# Ethernet_Interface.net
KiCad netlist of a schematic drawn in Altium Designer
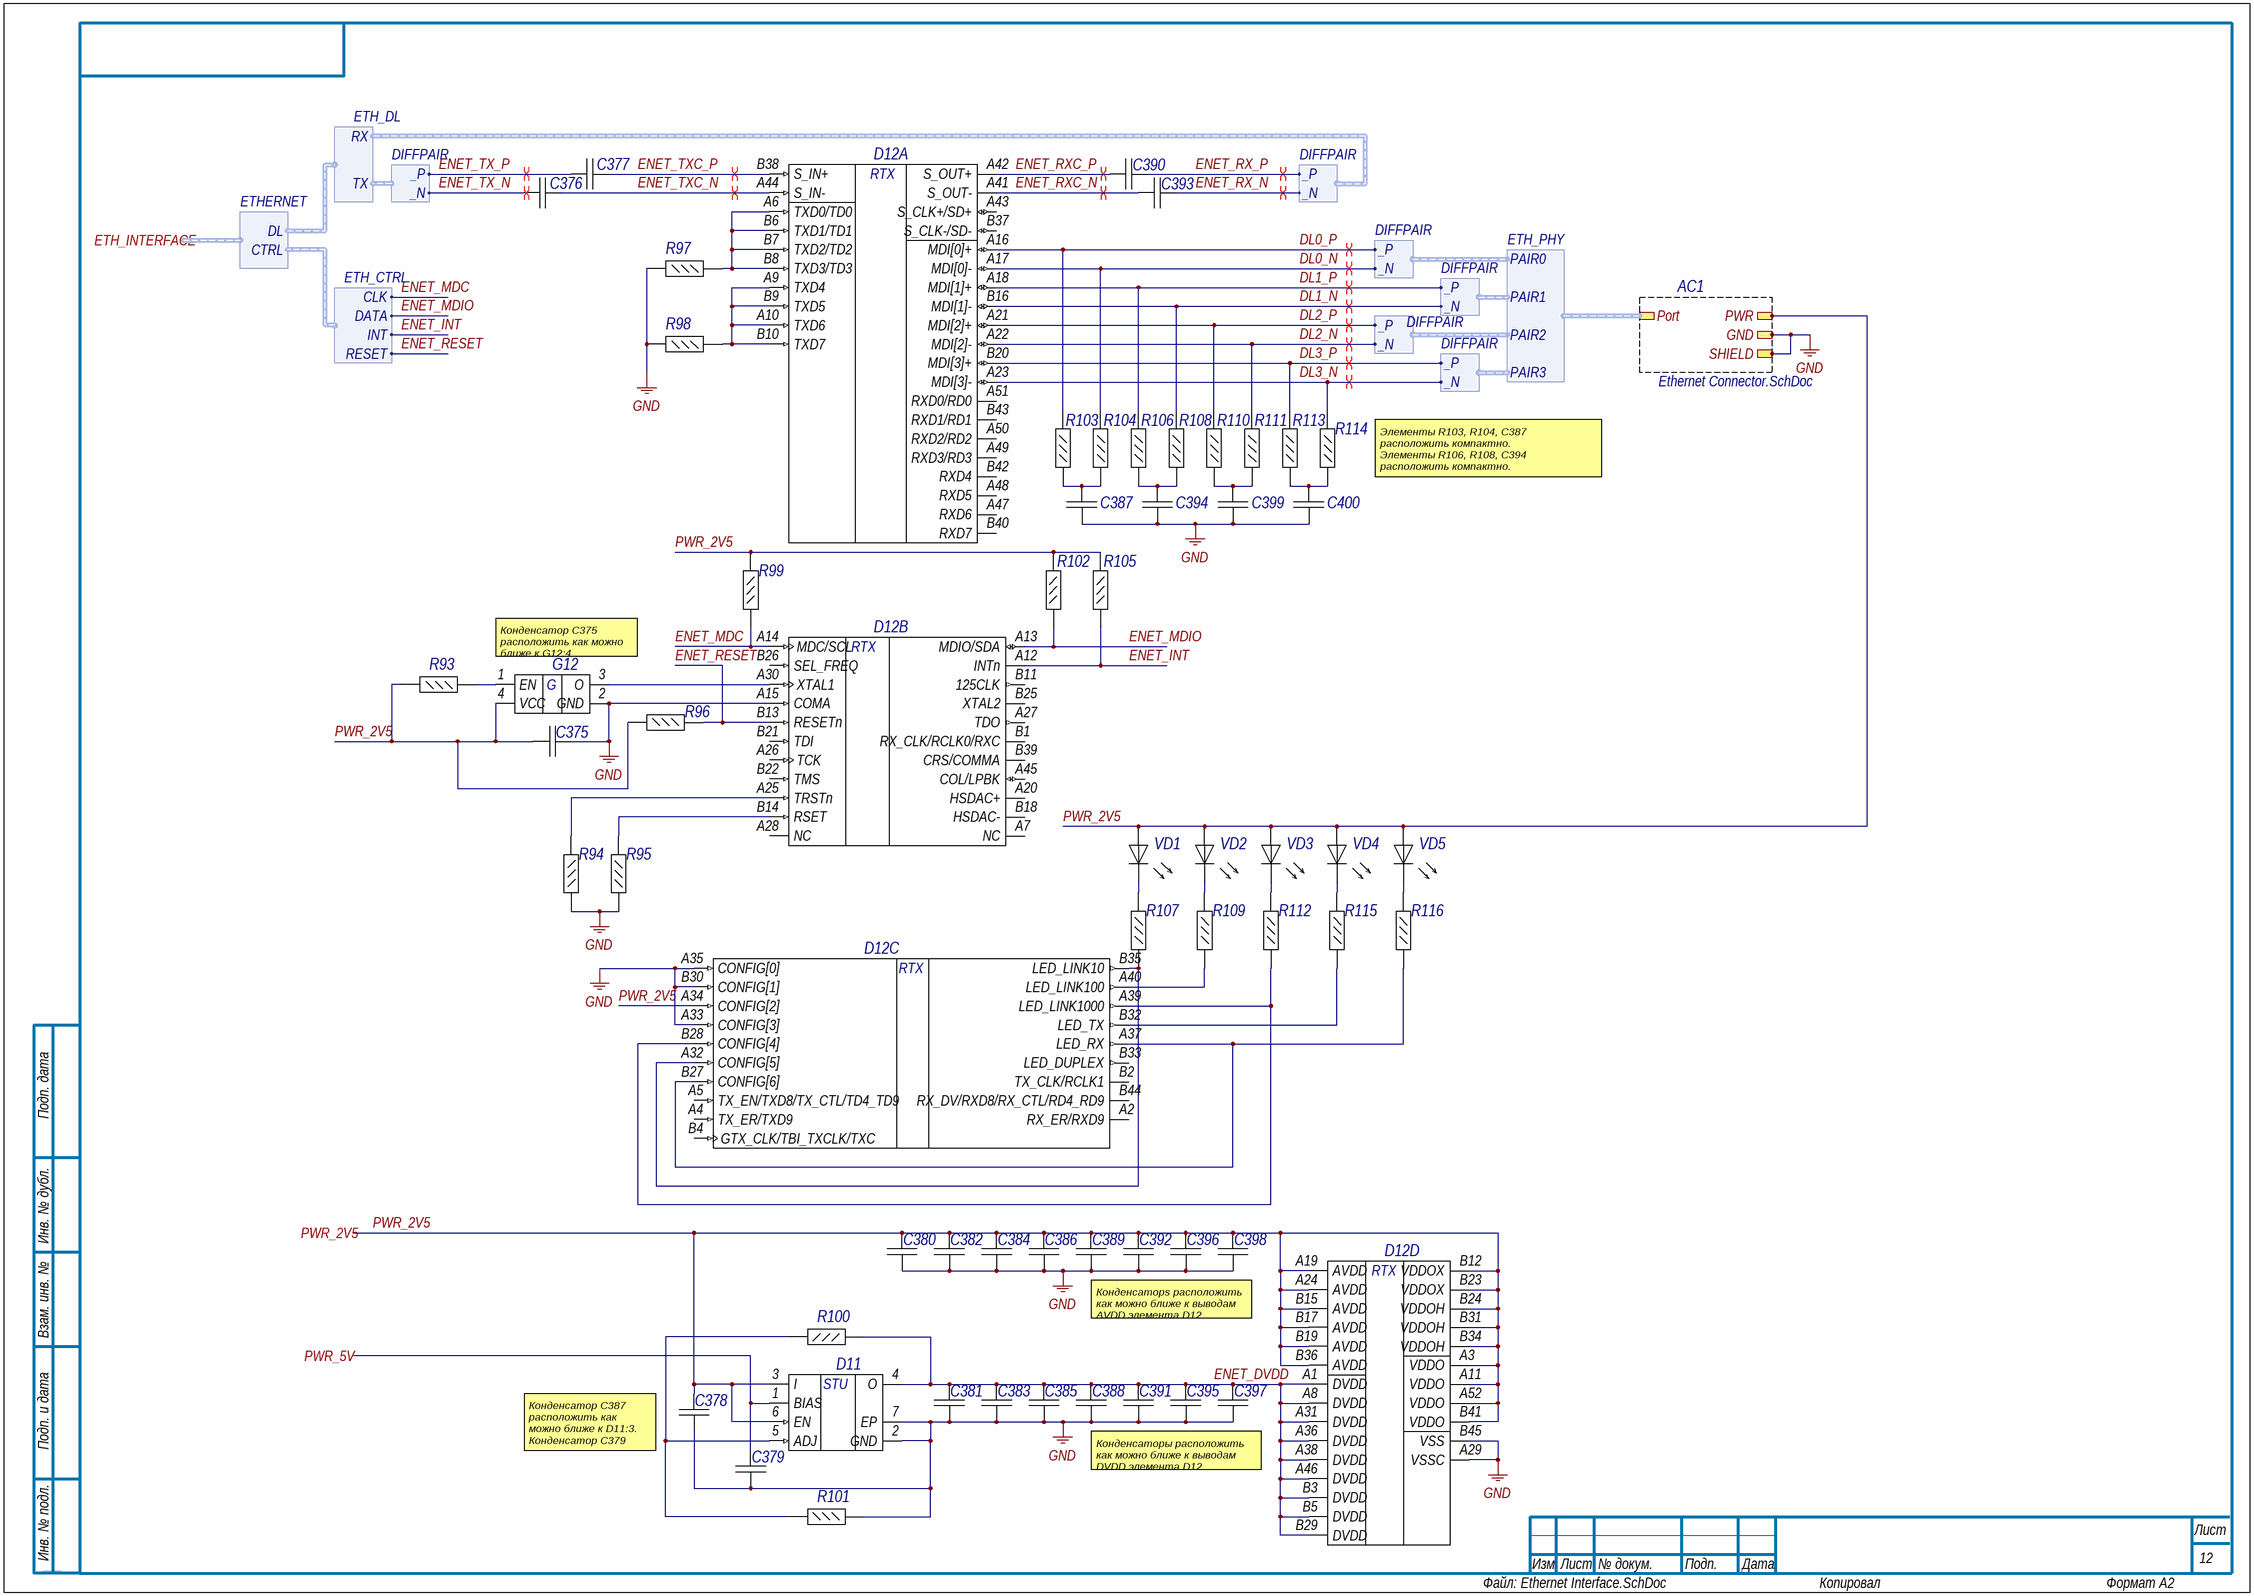
[diagram p0: Ethernet Interface.SchDoc]

(export (version "E")
  (design (tool "Eeschema 10.0.6"))
  (components
    (comp (ref "C375")
      (value "GRM155R71H103KA88D")
      (footprint "CAPC1005X55X25ML05T10")
      (description "Chip Capacitor, 10 nF, +/- 10%, 50 V, -55 to 125 degC, 0402 (1005 Metric), RoHS, Tape and Reel")
      (fields (field (name "TOLERANCE") "10%") (field (name "MANUFACTURER") "Basic Passives"))
      (libsource (lib "MiniPC DB") (part "CAP_NP"))
    )
    (comp (ref "C376")
      (value "C1005X7R1E104M")
      (footprint "CAPC1005X55X10LL05")
      (description "Chip Capacitor, 0.1 uF, +/- 20%, 25 V, -55 to 125 degC, 0402 (1005 Metric), RoHS, Tape and Reel")
      (fields (field (name "TOLERANCE") "20%"))
      (libsource (lib "MiniPC DB") (part "CAP_NP"))
    )
    (comp (ref "C377")
      (value "C1005X7R1E104M")
      (footprint "CAPC1005X55X10LL05")
      (description "Chip Capacitor, 0.1 uF, +/- 20%, 25 V, -55 to 125 degC, 0402 (1005 Metric), RoHS, Tape and Reel")
      (fields (field (name "TOLERANCE") "20%"))
      (libsource (lib "MiniPC DB") (part "CAP_NP"))
    )
    (comp (ref "C378")
      (value "C2012X5R1C106K085AC")
      (footprint "CAPC2013X100X20NL20")
      (description "Chip Capacitor, 10 uF, +/- 10%, 16 V, -55 to 85 degC, 0805 (2012 Metric), RoHS, Tape and Reel")
      (fields (field (name "TOLERANCE") "10%"))
      (libsource (lib "MiniPC DB") (part "CAP_NP"))
    )
    (comp (ref "C379")
      (value "CGB2A1X5R1E105K033BC")
      (footprint "CAPC1005X33X10LL5")
      (description "Chip Capacitor, 1 uF, +/- 10%, 25 V, -55 to 85 degC, 0402 (1005 Metric), RoHS, Tape and Reel")
      (fields (field (name "TOLERANCE") "10%"))
      (libsource (lib "MiniPC DB") (part "CAP_NP"))
    )
    (comp (ref "C380")
      (value "C1005X7R1E104M")
      (footprint "CAPC1005X55X10LL05")
      (description "Chip Capacitor, 0.1 uF, +/- 20%, 25 V, -55 to 125 degC, 0402 (1005 Metric), RoHS, Tape and Reel")
      (fields (field (name "TOLERANCE") "20%"))
      (libsource (lib "MiniPC DB") (part "CAP_NP"))
    )
    (comp (ref "C381")
      (value "GRM31CR61E226KE15L")
      (footprint "CAPC3216X180X55ML20T25")
      (description "Chip Capacitor, 22 uF, +/- 10%, 25 V, -55 to 85 degC, 1206 (3216 Metric), RoHS, Tape and Reel")
      (fields (field (name "TOLERANCE") "10%"))
      (libsource (lib "MiniPC DB") (part "CAP_NP"))
    )
    (comp (ref "C382")
      (value "C1005X7R1E104M")
      (footprint "CAPC1005X55X10LL05")
      (description "Chip Capacitor, 0.1 uF, +/- 20%, 25 V, -55 to 125 degC, 0402 (1005 Metric), RoHS, Tape and Reel")
      (fields (field (name "TOLERANCE") "20%"))
      (libsource (lib "MiniPC DB") (part "CAP_NP"))
    )
    (comp (ref "C383")
      (value "GRM188R61A225KE34x")
      (footprint "CAPC1608X90X35ML10T15")
      (description "Chip Capacitor, 2.2 uF, +/- 10%, 10 V, -55 to 85 degC, 0603 (1608 Metric), RoHS, Tape and Reel")
      (fields (field (name "TOLERANCE") "10%"))
      (libsource (lib "MiniPC DB") (part "CAP_NP"))
    )
    (comp (ref "C384")
      (value "C1005X7R1E104M")
      (footprint "CAPC1005X55X10LL05")
      (description "Chip Capacitor, 0.1 uF, +/- 20%, 25 V, -55 to 125 degC, 0402 (1005 Metric), RoHS, Tape and Reel")
      (fields (field (name "TOLERANCE") "20%"))
      (libsource (lib "MiniPC DB") (part "CAP_NP"))
    )
    (comp (ref "C385")
      (value "C1005X7R1E104M")
      (footprint "CAPC1005X55X10LL05")
      (description "Chip Capacitor, 0.1 uF, +/- 20%, 25 V, -55 to 125 degC, 0402 (1005 Metric), RoHS, Tape and Reel")
      (fields (field (name "TOLERANCE") "20%"))
      (libsource (lib "MiniPC DB") (part "CAP_NP"))
    )
    (comp (ref "C386")
      (value "C1005X7R1E104M")
      (footprint "CAPC1005X55X10LL05")
      (description "Chip Capacitor, 0.1 uF, +/- 20%, 25 V, -55 to 125 degC, 0402 (1005 Metric), RoHS, Tape and Reel")
      (fields (field (name "TOLERANCE") "20%"))
      (libsource (lib "MiniPC DB") (part "CAP_NP"))
    )
    (comp (ref "C387")
      (value "GRM155R71H103KA88D")
      (footprint "CAPC1005X55X25ML05T10")
      (description "Chip Capacitor, 10 nF, +/- 10%, 50 V, -55 to 125 degC, 0402 (1005 Metric), RoHS, Tape and Reel")
      (fields (field (name "TOLERANCE") "10%") (field (name "MANUFACTURER") "Basic Passives"))
      (libsource (lib "MiniPC DB") (part "CAP_NP"))
    )
    (comp (ref "C388")
      (value "C1005X7R1E104M")
      (footprint "CAPC1005X55X10LL05")
      (description "Chip Capacitor, 0.1 uF, +/- 20%, 25 V, -55 to 125 degC, 0402 (1005 Metric), RoHS, Tape and Reel")
      (fields (field (name "TOLERANCE") "20%"))
      (libsource (lib "MiniPC DB") (part "CAP_NP"))
    )
    (comp (ref "C389")
      (value "C1005X7R1E104M")
      (footprint "CAPC1005X55X10LL05")
      (description "Chip Capacitor, 0.1 uF, +/- 20%, 25 V, -55 to 125 degC, 0402 (1005 Metric), RoHS, Tape and Reel")
      (fields (field (name "TOLERANCE") "20%"))
      (libsource (lib "MiniPC DB") (part "CAP_NP"))
    )
    (comp (ref "C390")
      (value "C1005X7R1E104M")
      (footprint "CAPC1005X55X10LL05")
      (description "Chip Capacitor, 0.1 uF, +/- 20%, 25 V, -55 to 125 degC, 0402 (1005 Metric), RoHS, Tape and Reel")
      (fields (field (name "TOLERANCE") "20%"))
      (libsource (lib "MiniPC DB") (part "CAP_NP"))
    )
    (comp (ref "C391")
      (value "C1005X7R1E104M")
      (footprint "CAPC1005X55X10LL05")
      (description "Chip Capacitor, 0.1 uF, +/- 20%, 25 V, -55 to 125 degC, 0402 (1005 Metric), RoHS, Tape and Reel")
      (fields (field (name "TOLERANCE") "20%"))
      (libsource (lib "MiniPC DB") (part "CAP_NP"))
    )
    (comp (ref "C392")
      (value "C1005X7R1E104M")
      (footprint "CAPC1005X55X10LL05")
      (description "Chip Capacitor, 0.1 uF, +/- 20%, 25 V, -55 to 125 degC, 0402 (1005 Metric), RoHS, Tape and Reel")
      (fields (field (name "TOLERANCE") "20%"))
      (libsource (lib "MiniPC DB") (part "CAP_NP"))
    )
    (comp (ref "C393")
      (value "C1005X7R1E104M")
      (footprint "CAPC1005X55X10LL05")
      (description "Chip Capacitor, 0.1 uF, +/- 20%, 25 V, -55 to 125 degC, 0402 (1005 Metric), RoHS, Tape and Reel")
      (fields (field (name "TOLERANCE") "20%"))
      (libsource (lib "MiniPC DB") (part "CAP_NP"))
    )
    (comp (ref "C394")
      (value "GRM155R71H103KA88D")
      (footprint "CAPC1005X55X25ML05T10")
      (description "Chip Capacitor, 10 nF, +/- 10%, 50 V, -55 to 125 degC, 0402 (1005 Metric), RoHS, Tape and Reel")
      (fields (field (name "TOLERANCE") "10%") (field (name "MANUFACTURER") "Basic Passives"))
      (libsource (lib "MiniPC DB") (part "CAP_NP"))
    )
    (comp (ref "C395")
      (value "C1005X7R1E104M")
      (footprint "CAPC1005X55X10LL05")
      (description "Chip Capacitor, 0.1 uF, +/- 20%, 25 V, -55 to 125 degC, 0402 (1005 Metric), RoHS, Tape and Reel")
      (fields (field (name "TOLERANCE") "20%"))
      (libsource (lib "MiniPC DB") (part "CAP_NP"))
    )
    (comp (ref "C396")
      (value "C1005X7R1E104M")
      (footprint "CAPC1005X55X10LL05")
      (description "Chip Capacitor, 0.1 uF, +/- 20%, 25 V, -55 to 125 degC, 0402 (1005 Metric), RoHS, Tape and Reel")
      (fields (field (name "TOLERANCE") "20%"))
      (libsource (lib "MiniPC DB") (part "CAP_NP"))
    )
    (comp (ref "C397")
      (value "C1005X7R1E104M")
      (footprint "CAPC1005X55X10LL05")
      (description "Chip Capacitor, 0.1 uF, +/- 20%, 25 V, -55 to 125 degC, 0402 (1005 Metric), RoHS, Tape and Reel")
      (fields (field (name "TOLERANCE") "20%"))
      (libsource (lib "MiniPC DB") (part "CAP_NP"))
    )
    (comp (ref "C398")
      (value "C1005X7R1E104M")
      (footprint "CAPC1005X55X10LL05")
      (description "Chip Capacitor, 0.1 uF, +/- 20%, 25 V, -55 to 125 degC, 0402 (1005 Metric), RoHS, Tape and Reel")
      (fields (field (name "TOLERANCE") "20%"))
      (libsource (lib "MiniPC DB") (part "CAP_NP"))
    )
    (comp (ref "C399")
      (value "GRM155R71H103KA88D")
      (footprint "CAPC1005X55X25ML05T10")
      (description "Chip Capacitor, 10 nF, +/- 10%, 50 V, -55 to 125 degC, 0402 (1005 Metric), RoHS, Tape and Reel")
      (fields (field (name "TOLERANCE") "10%") (field (name "MANUFACTURER") "Basic Passives"))
      (libsource (lib "MiniPC DB") (part "CAP_NP"))
    )
    (comp (ref "C400")
      (value "GRM155R71H103KA88D")
      (footprint "CAPC1005X55X25ML05T10")
      (description "Chip Capacitor, 10 nF, +/- 10%, 50 V, -55 to 125 degC, 0402 (1005 Metric), RoHS, Tape and Reel")
      (fields (field (name "TOLERANCE") "10%") (field (name "MANUFACTURER") "Basic Passives"))
      (libsource (lib "MiniPC DB") (part "CAP_NP"))
    )
    (comp (ref "D11")
      (value "LTC3025EDC-1#PBF")
      (footprint "LT-DC6-6_V")
      (fields (field (name "MANUFACTURER") "Linear Technology"))
      (libsource (lib "MiniPC DB") (part "LTC3025"))
    )
    (comp (ref "D12")
      (value "88E1111-B2-NDC2C000")
      (footprint "MARV-NDC96")
      (description "Integrated 10/100/1000 Ultra Gigabit Ethernet Transceiver, Commercial Grade, 96-Pin QFN, RoHS")
      (libsource (lib "MiniPC DB") (part "88E1111"))
    )
    (comp (ref "G12")
      (value "SG-310SDF 25.0000M-B3")
      (footprint "EPSON-SG-310-4_V")
      (description "Crystal Oscillator (SPXO), 2.5 V, 25 MHz, -20 to 70 degC, 4-Pin SMD, RoHS, Tape and Reel")
      (libsource (lib "MiniPC DB") (part "GEN"))
    )
    (comp (ref "R93")
      (value "ERJ-2RKF1002X")
      (footprint "RESC1005X40X25LL05T05")
      (description "Chip Resistor, 10 KOhm, +/- 1%, 100 mW, -55 to 155 degC, 0402 (1005 Metric), RoHS, Tape and Reel")
      (fields (field (name "TOLERANCE") "1%") (field (name "MANUFACTURER") "Basic Passives"))
      (libsource (lib "MiniPC DB") (part "RES-0.05"))
    )
    (comp (ref "R94")
      (value "ERJ-2RKF4701X")
      (footprint "RESC1005X40X25LL05T05")
      (description "Chip Resistor, 4.7 KOhm, +/- 1%, 0.1 W, -55 to 155 degC, 0402 (1005 Metric), RoHS, Tape and Reel")
      (fields (field (name "TOLERANCE") "1%"))
      (libsource (lib "") (part "RES-0.05_3"))
    )
    (comp (ref "R95")
      (value "ERJ-2RKF4991X")
      (footprint "RESC1005X40X25LL05T05")
      (description "Chip Resistor, 4.99 KOhm, +/- 1%, 100 mW, -55 to 155 degC, 0402 (1005 Metric), RoHS, Tape and Reel")
      (fields (field (name "TOLERANCE") "1%") (field (name "MANUFACTURER") "Basic Passives"))
      (libsource (lib "") (part "RES-0.05_1"))
    )
    (comp (ref "R96")
      (value "ERJ-2RKF4701X")
      (footprint "RESC1005X40X25LL05T05")
      (description "Chip Resistor, 4.7 KOhm, +/- 1%, 0.1 W, -55 to 155 degC, 0402 (1005 Metric), RoHS, Tape and Reel")
      (fields (field (name "TOLERANCE") "1%"))
      (libsource (lib "") (part "RES-0.05_1"))
    )
    (comp (ref "R97")
      (value "ERJ-2GE0R00X")
      (footprint "RESC1005X40X25LL05T05")
      (description "Chip Resistor, 0 mOhm, +/- 5%, 100 mW, -55 to 155 degC, 0402 (1005 Metric), RoHS, Tape and Reel")
      (fields (field (name "TOLERANCE") "5%") (field (name "MANUFACTURER") "Basic Passives"))
      (libsource (lib "MiniPC DB") (part "RES-0.05"))
    )
    (comp (ref "R98")
      (value "ERJ-2GE0R00X")
      (footprint "RESC1005X40X25LL05T05")
      (description "Chip Resistor, 0 mOhm, +/- 5%, 100 mW, -55 to 155 degC, 0402 (1005 Metric), RoHS, Tape and Reel")
      (fields (field (name "TOLERANCE") "5%") (field (name "MANUFACTURER") "Basic Passives"))
      (libsource (lib "MiniPC DB") (part "RES-0.05"))
    )
    (comp (ref "R99")
      (value "ERJ-2RKF4701X")
      (footprint "RESC1005X40X25LL05T05")
      (description "Chip Resistor, 4.7 KOhm, +/- 1%, 0.1 W, -55 to 155 degC, 0402 (1005 Metric), RoHS, Tape and Reel")
      (fields (field (name "TOLERANCE") "1%"))
      (libsource (lib "") (part "RES-0.05_2"))
    )
    (comp (ref "R100")
      (value "ERJ-2RKF1502X")
      (footprint "RESC1005X40X25LL05T05")
      (description "Chip Resistor, 15 KOhm, +/- 1%, 100 mW, -55 to 155 degC, 0402 (1005 Metric), RoHS, Tape and Reel")
      (fields (field (name "TOLERANCE") "1%") (field (name "MANUFACTURER") "Basic Passives"))
      (libsource (lib "") (part "RES-0.05_2"))
    )
    (comp (ref "R101")
      (value "ERJ-2RKF1002X")
      (footprint "RESC1005X40X25LL05T05")
      (description "Chip Resistor, 10 KOhm, +/- 1%, 100 mW, -55 to 155 degC, 0402 (1005 Metric), RoHS, Tape and Reel")
      (fields (field (name "TOLERANCE") "1%") (field (name "MANUFACTURER") "Basic Passives"))
      (libsource (lib "") (part "RES-0.05_1"))
    )
    (comp (ref "R102")
      (value "NRC04F49R9TRF")
      (footprint "RESC1005X35X25NL8T10")
      (description "Chip Resistor, 49.9 Ohm, +/- 1%, 0.06 W, -55 to 155 degC, 0402 (1005 Metric), RoHS, Tape and Reel")
      (fields (field (name "TOLERANCE") "1%"))
      (libsource (lib "") (part "RES-0.05_2"))
    )
    (comp (ref "R103")
      (value "NRC04F49R9TRF")
      (footprint "RESC1005X35X25NL8T10")
      (description "Chip Resistor, 49.9 Ohm, +/- 1%, 0.06 W, -55 to 155 degC, 0402 (1005 Metric), RoHS, Tape and Reel")
      (fields (field (name "TOLERANCE") "1%"))
      (libsource (lib "") (part "RES-0.05_1"))
    )
    (comp (ref "R104")
      (value "NRC04F49R9TRF")
      (footprint "RESC1005X35X25NL8T10")
      (description "Chip Resistor, 49.9 Ohm, +/- 1%, 0.06 W, -55 to 155 degC, 0402 (1005 Metric), RoHS, Tape and Reel")
      (fields (field (name "TOLERANCE") "1%"))
      (libsource (lib "") (part "RES-0.05_1"))
    )
    (comp (ref "R105")
      (value "ERJ-2RKF4701X")
      (footprint "RESC1005X40X25LL05T05")
      (description "Chip Resistor, 4.7 KOhm, +/- 1%, 0.1 W, -55 to 155 degC, 0402 (1005 Metric), RoHS, Tape and Reel")
      (fields (field (name "TOLERANCE") "1%"))
      (libsource (lib "") (part "RES-0.05_2"))
    )
    (comp (ref "R106")
      (value "NRC04F49R9TRF")
      (footprint "RESC1005X35X25NL8T10")
      (description "Chip Resistor, 49.9 Ohm, +/- 1%, 0.06 W, -55 to 155 degC, 0402 (1005 Metric), RoHS, Tape and Reel")
      (fields (field (name "TOLERANCE") "1%"))
      (libsource (lib "") (part "RES-0.05_1"))
    )
    (comp (ref "R107")
      (value "ERJ-2RKF2400X")
      (footprint "RESC1005X40X25LL05T05")
      (description "Chip Resistor, 240 Ohm, +/- 1%, 100 mW, -55 to 155 degC, 0402 (1005 Metric), RoHS, Tape and Reel")
      (fields (field (name "TOLERANCE") "1%"))
      (libsource (lib "") (part "RES-0.05_1"))
    )
    (comp (ref "R108")
      (value "NRC04F49R9TRF")
      (footprint "RESC1005X35X25NL8T10")
      (description "Chip Resistor, 49.9 Ohm, +/- 1%, 0.06 W, -55 to 155 degC, 0402 (1005 Metric), RoHS, Tape and Reel")
      (fields (field (name "TOLERANCE") "1%"))
      (libsource (lib "") (part "RES-0.05_1"))
    )
    (comp (ref "R109")
      (value "ERJ-2RKF2400X")
      (footprint "RESC1005X40X25LL05T05")
      (description "Chip Resistor, 240 Ohm, +/- 1%, 100 mW, -55 to 155 degC, 0402 (1005 Metric), RoHS, Tape and Reel")
      (fields (field (name "TOLERANCE") "1%"))
      (libsource (lib "") (part "RES-0.05_1"))
    )
    (comp (ref "R110")
      (value "NRC04F49R9TRF")
      (footprint "RESC1005X35X25NL8T10")
      (description "Chip Resistor, 49.9 Ohm, +/- 1%, 0.06 W, -55 to 155 degC, 0402 (1005 Metric), RoHS, Tape and Reel")
      (fields (field (name "TOLERANCE") "1%"))
      (libsource (lib "") (part "RES-0.05_1"))
    )
    (comp (ref "R111")
      (value "NRC04F49R9TRF")
      (footprint "RESC1005X35X25NL8T10")
      (description "Chip Resistor, 49.9 Ohm, +/- 1%, 0.06 W, -55 to 155 degC, 0402 (1005 Metric), RoHS, Tape and Reel")
      (fields (field (name "TOLERANCE") "1%"))
      (libsource (lib "") (part "RES-0.05_1"))
    )
    (comp (ref "R112")
      (value "ERJ-2RKF2400X")
      (footprint "RESC1005X40X25LL05T05")
      (description "Chip Resistor, 240 Ohm, +/- 1%, 100 mW, -55 to 155 degC, 0402 (1005 Metric), RoHS, Tape and Reel")
      (fields (field (name "TOLERANCE") "1%"))
      (libsource (lib "") (part "RES-0.05_1"))
    )
    (comp (ref "R113")
      (value "NRC04F49R9TRF")
      (footprint "RESC1005X35X25NL8T10")
      (description "Chip Resistor, 49.9 Ohm, +/- 1%, 0.06 W, -55 to 155 degC, 0402 (1005 Metric), RoHS, Tape and Reel")
      (fields (field (name "TOLERANCE") "1%"))
      (libsource (lib "") (part "RES-0.05_1"))
    )
    (comp (ref "R114")
      (value "NRC04F49R9TRF")
      (footprint "RESC1005X35X25NL8T10")
      (description "Chip Resistor, 49.9 Ohm, +/- 1%, 0.06 W, -55 to 155 degC, 0402 (1005 Metric), RoHS, Tape and Reel")
      (fields (field (name "TOLERANCE") "1%"))
      (libsource (lib "") (part "RES-0.05_1"))
    )
    (comp (ref "R115")
      (value "ERJ-2RKF2400X")
      (footprint "RESC1005X40X25LL05T05")
      (description "Chip Resistor, 240 Ohm, +/- 1%, 100 mW, -55 to 155 degC, 0402 (1005 Metric), RoHS, Tape and Reel")
      (fields (field (name "TOLERANCE") "1%"))
      (libsource (lib "") (part "RES-0.05_1"))
    )
    (comp (ref "R116")
      (value "ERJ-2RKF2400X")
      (footprint "RESC1005X40X25LL05T05")
      (description "Chip Resistor, 240 Ohm, +/- 1%, 100 mW, -55 to 155 degC, 0402 (1005 Metric), RoHS, Tape and Reel")
      (fields (field (name "TOLERANCE") "1%"))
      (libsource (lib "") (part "RES-0.05_1"))
    )
    (comp (ref "VD1")
      (value "150060VS75000")
      (footprint "0603_A")
      (description "SMD mono-color Chip LED, WL-SMCW, Bright Green")
      (fields (field (name "MANUFACTURER") "Wuerth Elektronik"))
      (libsource (lib "MiniPC DB") (part "LED"))
    )
    (comp (ref "VD2")
      (value "150060VS75000")
      (footprint "0603_A")
      (description "SMD mono-color Chip LED, WL-SMCW, Bright Green")
      (fields (field (name "MANUFACTURER") "Wuerth Elektronik"))
      (libsource (lib "MiniPC DB") (part "LED"))
    )
    (comp (ref "VD3")
      (value "150060VS75000")
      (footprint "0603_A")
      (description "SMD mono-color Chip LED, WL-SMCW, Bright Green")
      (fields (field (name "MANUFACTURER") "Wuerth Elektronik"))
      (libsource (lib "MiniPC DB") (part "LED"))
    )
    (comp (ref "VD4")
      (value "150060VS75000")
      (footprint "0603_A")
      (description "SMD mono-color Chip LED, WL-SMCW, Bright Green")
      (fields (field (name "MANUFACTURER") "Wuerth Elektronik"))
      (libsource (lib "MiniPC DB") (part "LED"))
    )
    (comp (ref "VD5")
      (value "150060VS75000")
      (footprint "0603_A")
      (description "SMD mono-color Chip LED, WL-SMCW, Bright Green")
      (fields (field (name "MANUFACTURER") "Wuerth Elektronik"))
      (libsource (lib "MiniPC DB") (part "LED"))
    )
  )
  (nets
    (net (code "5") (name "/DL0_N") (class "Default")
      (node (ref "D12") (pin "A17") (pinfunction "MDI[0]-_A17") (pintype "bidirectional"))
      (node (ref "R104") (pin "1") (pinfunction "1_1") (pintype "passive"))
    )
    (net (code "6") (name "/DL0_P") (class "Default")
      (node (ref "D12") (pin "A16") (pinfunction "MDI[0]+_A16") (pintype "bidirectional"))
      (node (ref "R103") (pin "1") (pinfunction "1_1") (pintype "passive"))
    )
    (net (code "7") (name "/DL1_N") (class "Default")
      (node (ref "D12") (pin "B16") (pinfunction "MDI[1]-_B16") (pintype "bidirectional"))
      (node (ref "R108") (pin "1") (pinfunction "1_1") (pintype "passive"))
    )
    (net (code "8") (name "/DL1_P") (class "Default")
      (node (ref "D12") (pin "A18") (pinfunction "MDI[1]+_A18") (pintype "bidirectional"))
      (node (ref "R106") (pin "1") (pinfunction "1_1") (pintype "passive"))
    )
    (net (code "9") (name "/DL2_N") (class "Default")
      (node (ref "D12") (pin "A22") (pinfunction "MDI[2]-_A22") (pintype "bidirectional"))
      (node (ref "R111") (pin "1") (pinfunction "1_1") (pintype "passive"))
    )
    (net (code "10") (name "/DL2_P") (class "Default")
      (node (ref "D12") (pin "A21") (pinfunction "MDI[2]+_A21") (pintype "bidirectional"))
      (node (ref "R110") (pin "1") (pinfunction "1_1") (pintype "passive"))
    )
    (net (code "11") (name "/DL3_N") (class "Default")
      (node (ref "D12") (pin "A23") (pinfunction "MDI[3]-_A23") (pintype "bidirectional"))
      (node (ref "R114") (pin "1") (pinfunction "1_1") (pintype "passive"))
    )
    (net (code "12") (name "/DL3_P") (class "Default")
      (node (ref "D12") (pin "B20") (pinfunction "MDI[3]+_B20") (pintype "bidirectional"))
      (node (ref "R113") (pin "1") (pinfunction "1_1") (pintype "passive"))
    )
    (net (code "13") (name "/ENET_DVDD") (class "Default")
      (node (ref "C381") (pin "2") (pinfunction "2_2") (pintype "passive"))
      (node (ref "C383") (pin "2") (pinfunction "2_2") (pintype "passive"))
      (node (ref "C385") (pin "2") (pinfunction "2_2") (pintype "passive"))
      (node (ref "C388") (pin "2") (pinfunction "2_2") (pintype "passive"))
      (node (ref "C391") (pin "2") (pinfunction "2_2") (pintype "passive"))
      (node (ref "C395") (pin "2") (pinfunction "2_2") (pintype "passive"))
      (node (ref "C397") (pin "2") (pinfunction "2_2") (pintype "passive"))
      (node (ref "D11") (pin "4") (pinfunction "O_4") (pintype "power_in"))
      (node (ref "D12") (pin "A1") (pinfunction "DVDD_A1") (pintype "power_in"))
      (node (ref "D12") (pin "A31") (pinfunction "DVDD_A31") (pintype "power_in"))
      (node (ref "D12") (pin "A36") (pinfunction "DVDD_A36") (pintype "power_in"))
      (node (ref "D12") (pin "A38") (pinfunction "DVDD_A38") (pintype "power_in"))
      (node (ref "D12") (pin "A46") (pinfunction "DVDD_A46") (pintype "power_in"))
      (node (ref "D12") (pin "A8") (pinfunction "DVDD_A8") (pintype "power_in"))
      (node (ref "D12") (pin "B29") (pinfunction "DVDD_B29") (pintype "power_in"))
      (node (ref "D12") (pin "B3") (pinfunction "DVDD_B3") (pintype "power_in"))
      (node (ref "D12") (pin "B5") (pinfunction "DVDD_B5") (pintype "power_in"))
      (node (ref "R100") (pin "2") (pinfunction "2_2") (pintype "passive"))
    )
    (net (code "14") (name "/ENET_INT") (class "Default")
      (node (ref "D12") (pin "A12") (pinfunction "INTn_A12") (pintype "passive"))
      (node (ref "R105") (pin "1") (pinfunction "1_1") (pintype "passive"))
    )
    (net (code "15") (name "/ENET_MDC") (class "Default")
      (node (ref "D12") (pin "A14") (pinfunction "MDC/SCL_A14") (pintype "input"))
      (node (ref "R99") (pin "1") (pinfunction "1_1") (pintype "passive"))
    )
    (net (code "16") (name "/ENET_MDIO") (class "Default")
      (node (ref "D12") (pin "A13") (pinfunction "MDIO/SDA_A13") (pintype "bidirectional"))
      (node (ref "R102") (pin "1") (pinfunction "1_1") (pintype "passive"))
    )
    (net (code "17") (name "/ENET_RESET") (class "Default")
      (node (ref "D12") (pin "B13") (pinfunction "RESETn_B13") (pintype "input"))
      (node (ref "R96") (pin "1") (pinfunction "1_1") (pintype "passive"))
    )
    (net (code "18") (name "/ENET_RXC_N") (class "Default")
      (node (ref "C393") (pin "2") (pinfunction "2_2") (pintype "passive"))
      (node (ref "D12") (pin "A41") (pinfunction "S_OUT-_A41") (pintype "tri_state"))
    )
    (net (code "19") (name "/ENET_RXC_P") (class "Default")
      (node (ref "C390") (pin "2") (pinfunction "2_2") (pintype "passive"))
      (node (ref "D12") (pin "A42") (pinfunction "S_OUT+_A42") (pintype "tri_state"))
    )
    (net (code "20") (name "/ENET_RX_N") (class "Default")
      (node (ref "C393") (pin "1") (pinfunction "1_1") (pintype "passive"))
    )
    (net (code "21") (name "/ENET_RX_P") (class "Default")
      (node (ref "C390") (pin "1") (pinfunction "1_1") (pintype "passive"))
    )
    (net (code "22") (name "/ENET_TXC_N") (class "Default")
      (node (ref "C376") (pin "2") (pinfunction "2_2") (pintype "passive"))
      (node (ref "D12") (pin "A44") (pinfunction "S_IN-_A44") (pintype "input"))
    )
    (net (code "23") (name "/ENET_TXC_P") (class "Default")
      (node (ref "C377") (pin "2") (pinfunction "2_2") (pintype "passive"))
      (node (ref "D12") (pin "B38") (pinfunction "S_IN+_B38") (pintype "input"))
    )
    (net (code "24") (name "/ENET_TX_N") (class "Default")
      (node (ref "C376") (pin "1") (pinfunction "1_1") (pintype "passive"))
    )
    (net (code "25") (name "/ENET_TX_P") (class "Default")
      (node (ref "C377") (pin "1") (pinfunction "1_1") (pintype "passive"))
    )
    (net (code "26") (name "/PWR_2V5") (class "Default")
      (node (ref "C375") (pin "2") (pinfunction "2_2") (pintype "passive"))
      (node (ref "C378") (pin "2") (pinfunction "2_2") (pintype "passive"))
      (node (ref "C380") (pin "2") (pinfunction "2_2") (pintype "passive"))
      (node (ref "C382") (pin "2") (pinfunction "2_2") (pintype "passive"))
      (node (ref "C384") (pin "2") (pinfunction "2_2") (pintype "passive"))
      (node (ref "C386") (pin "2") (pinfunction "2_2") (pintype "passive"))
      (node (ref "C389") (pin "2") (pinfunction "2_2") (pintype "passive"))
      (node (ref "C392") (pin "2") (pinfunction "2_2") (pintype "passive"))
      (node (ref "C396") (pin "2") (pinfunction "2_2") (pintype "passive"))
      (node (ref "C398") (pin "2") (pinfunction "2_2") (pintype "passive"))
      (node (ref "D11") (pin "3") (pinfunction "I_3") (pintype "passive"))
      (node (ref "D11") (pin "6") (pinfunction "EN_6") (pintype "input"))
      (node (ref "D12") (pin "A11") (pinfunction "VDDO_A11") (pintype "power_in"))
      (node (ref "D12") (pin "A19") (pinfunction "AVDD_A19") (pintype "power_in"))
      (node (ref "D12") (pin "A24") (pinfunction "AVDD_A24") (pintype "power_in"))
      (node (ref "D12") (pin "A3") (pinfunction "VDDO_A3") (pintype "power_in"))
      (node (ref "D12") (pin "A34") (pinfunction "CONFIG[2]_A34") (pintype "input"))
      (node (ref "D12") (pin "A52") (pinfunction "VDDO_A52") (pintype "power_in"))
      (node (ref "D12") (pin "B12") (pinfunction "VDDOX_B12") (pintype "power_in"))
      (node (ref "D12") (pin "B15") (pinfunction "AVDD_B15") (pintype "power_in"))
      (node (ref "D12") (pin "B17") (pinfunction "AVDD_B17") (pintype "power_in"))
      (node (ref "D12") (pin "B19") (pinfunction "AVDD_B19") (pintype "power_in"))
      (node (ref "D12") (pin "B23") (pinfunction "VDDOX_B23") (pintype "power_in"))
      (node (ref "D12") (pin "B24") (pinfunction "VDDOH_B24") (pintype "power_in"))
      (node (ref "D12") (pin "B31") (pinfunction "VDDOH_B31") (pintype "power_in"))
      (node (ref "D12") (pin "B34") (pinfunction "VDDOH_B34") (pintype "power_in"))
      (node (ref "D12") (pin "B36") (pinfunction "AVDD_B36") (pintype "power_in"))
      (node (ref "D12") (pin "B41") (pinfunction "VDDO_B41") (pintype "power_in"))
      (node (ref "G12") (pin "4") (pinfunction "VCC_4") (pintype "passive"))
      (node (ref "R102") (pin "2") (pinfunction "2_2") (pintype "passive"))
      (node (ref "R105") (pin "2") (pinfunction "2_2") (pintype "passive"))
      (node (ref "R93") (pin "1") (pinfunction "1_1") (pintype "passive"))
      (node (ref "R96") (pin "2") (pinfunction "2_2") (pintype "passive"))
      (node (ref "R99") (pin "2") (pinfunction "2_2") (pintype "passive"))
      (node (ref "VD1") (pin "2") (pinfunction "A_2") (pintype "passive"))
      (node (ref "VD2") (pin "2") (pinfunction "A_2") (pintype "passive"))
      (node (ref "VD3") (pin "2") (pinfunction "A_2") (pintype "passive"))
      (node (ref "VD4") (pin "2") (pinfunction "A_2") (pintype "passive"))
      (node (ref "VD5") (pin "2") (pinfunction "A_2") (pintype "passive"))
    )
    (net (code "27") (name "/PWR_5V") (class "Default")
      (node (ref "C379") (pin "2") (pinfunction "2_2") (pintype "passive"))
      (node (ref "D11") (pin "1") (pinfunction "BIAS_1") (pintype "power_in"))
    )
    (net (code "33") (name "GND") (class "Default")
      (node (ref "C375") (pin "1") (pinfunction "1_1") (pintype "passive"))
      (node (ref "C378") (pin "1") (pinfunction "1_1") (pintype "passive"))
      (node (ref "C379") (pin "1") (pinfunction "1_1") (pintype "passive"))
      (node (ref "C380") (pin "1") (pinfunction "1_1") (pintype "passive"))
      (node (ref "C381") (pin "1") (pinfunction "1_1") (pintype "passive"))
      (node (ref "C382") (pin "1") (pinfunction "1_1") (pintype "passive"))
      (node (ref "C383") (pin "1") (pinfunction "1_1") (pintype "passive"))
      (node (ref "C384") (pin "1") (pinfunction "1_1") (pintype "passive"))
      (node (ref "C385") (pin "1") (pinfunction "1_1") (pintype "passive"))
      (node (ref "C386") (pin "1") (pinfunction "1_1") (pintype "passive"))
      (node (ref "C387") (pin "2") (pinfunction "2_2") (pintype "passive"))
      (node (ref "C388") (pin "1") (pinfunction "1_1") (pintype "passive"))
      (node (ref "C389") (pin "1") (pinfunction "1_1") (pintype "passive"))
      (node (ref "C391") (pin "1") (pinfunction "1_1") (pintype "passive"))
      (node (ref "C392") (pin "1") (pinfunction "1_1") (pintype "passive"))
      (node (ref "C394") (pin "2") (pinfunction "2_2") (pintype "passive"))
      (node (ref "C395") (pin "1") (pinfunction "1_1") (pintype "passive"))
      (node (ref "C396") (pin "1") (pinfunction "1_1") (pintype "passive"))
      (node (ref "C397") (pin "1") (pinfunction "1_1") (pintype "passive"))
      (node (ref "C398") (pin "1") (pinfunction "1_1") (pintype "passive"))
      (node (ref "C399") (pin "2") (pinfunction "2_2") (pintype "passive"))
      (node (ref "C400") (pin "2") (pinfunction "2_2") (pintype "passive"))
      (node (ref "D11") (pin "2") (pinfunction "GND_2") (pintype "passive"))
      (node (ref "D11") (pin "7") (pinfunction "EP_7") (pintype "passive"))
      (node (ref "D12") (pin "A15") (pinfunction "COMA_A15") (pintype "input"))
      (node (ref "D12") (pin "A29") (pinfunction "VSSC_A29") (pintype "power_in"))
      (node (ref "D12") (pin "A33") (pinfunction "CONFIG[3]_A33") (pintype "input"))
      (node (ref "D12") (pin "A35") (pinfunction "CONFIG[0]_A35") (pintype "input"))
      (node (ref "D12") (pin "B30") (pinfunction "CONFIG[1]_B30") (pintype "input"))
      (node (ref "D12") (pin "B45") (pinfunction "VSS_B45") (pintype "power_in"))
      (node (ref "G12") (pin "2") (pinfunction "GND_2") (pintype "passive"))
      (node (ref "R101") (pin "1") (pinfunction "1_1") (pintype "passive"))
      (node (ref "R94") (pin "2") (pinfunction "2_2") (pintype "passive"))
      (node (ref "R95") (pin "2") (pinfunction "2_2") (pintype "passive"))
      (node (ref "R97") (pin "1") (pinfunction "1_1") (pintype "passive"))
      (node (ref "R98") (pin "1") (pinfunction "1_1") (pintype "passive"))
    )
    (net (code "34") (name "Net-(C387-Pad1)") (class "Default")
      (node (ref "C387") (pin "1") (pinfunction "1_1") (pintype "passive"))
      (node (ref "R103") (pin "2") (pinfunction "2_2") (pintype "passive"))
      (node (ref "R104") (pin "2") (pinfunction "2_2") (pintype "passive"))
    )
    (net (code "35") (name "Net-(C394-Pad1)") (class "Default")
      (node (ref "C394") (pin "1") (pinfunction "1_1") (pintype "passive"))
      (node (ref "R106") (pin "2") (pinfunction "2_2") (pintype "passive"))
      (node (ref "R108") (pin "2") (pinfunction "2_2") (pintype "passive"))
    )
    (net (code "36") (name "Net-(C399-Pad1)") (class "Default")
      (node (ref "C399") (pin "1") (pinfunction "1_1") (pintype "passive"))
      (node (ref "R110") (pin "2") (pinfunction "2_2") (pintype "passive"))
      (node (ref "R111") (pin "2") (pinfunction "2_2") (pintype "passive"))
    )
    (net (code "37") (name "Net-(C400-Pad1)") (class "Default")
      (node (ref "C400") (pin "1") (pinfunction "1_1") (pintype "passive"))
      (node (ref "R113") (pin "2") (pinfunction "2_2") (pintype "passive"))
      (node (ref "R114") (pin "2") (pinfunction "2_2") (pintype "passive"))
    )
    (net (code "38") (name "Net-(D11-ADJ)") (class "Default")
      (node (ref "D11") (pin "5") (pinfunction "ADJ_5") (pintype "input"))
      (node (ref "R100") (pin "1") (pinfunction "1_1") (pintype "passive"))
      (node (ref "R101") (pin "2") (pinfunction "2_2") (pintype "passive"))
    )
    (net (code "39") (name "Net-(D12A-TXD0{slash}TD0)") (class "Default")
      (node (ref "D12") (pin "A6") (pinfunction "TXD0/TD0_A6") (pintype "input"))
      (node (ref "D12") (pin "B6") (pinfunction "TXD1/TD1_B6") (pintype "input"))
      (node (ref "D12") (pin "B7") (pinfunction "TXD2/TD2_B7") (pintype "input"))
      (node (ref "D12") (pin "B8") (pinfunction "TXD3/TD3_B8") (pintype "input"))
      (node (ref "R97") (pin "2") (pinfunction "2_2") (pintype "passive"))
    )
    (net (code "40") (name "Net-(D12A-TXD4)") (class "Default")
      (node (ref "D12") (pin "A10") (pinfunction "TXD6_A10") (pintype "input"))
      (node (ref "D12") (pin "A9") (pinfunction "TXD4_A9") (pintype "input"))
      (node (ref "D12") (pin "B10") (pinfunction "TXD7_B10") (pintype "input"))
      (node (ref "D12") (pin "B9") (pinfunction "TXD5_B9") (pintype "input"))
      (node (ref "R98") (pin "2") (pinfunction "2_2") (pintype "passive"))
    )
    (net (code "41") (name "Net-(D12B-RSET)") (class "Default")
      (node (ref "D12") (pin "B14") (pinfunction "RSET_B14") (pintype "input"))
      (node (ref "R95") (pin "1") (pinfunction "1_1") (pintype "passive"))
    )
    (net (code "42") (name "Net-(D12B-TRSTn)") (class "Default")
      (node (ref "D12") (pin "A25") (pinfunction "TRSTn_A25") (pintype "input"))
      (node (ref "R94") (pin "1") (pinfunction "1_1") (pintype "passive"))
    )
    (net (code "43") (name "Net-(D12B-XTAL1)") (class "Default")
      (node (ref "D12") (pin "A30") (pinfunction "XTAL1_A30") (pintype "input"))
      (node (ref "G12") (pin "3") (pinfunction "O_3") (pintype "passive"))
    )
    (net (code "44") (name "Net-(D12C-CONFIG[4])") (class "Default")
      (node (ref "D12") (pin "A39") (pinfunction "LED_LINK1000_A39") (pintype "output"))
      (node (ref "D12") (pin "B28") (pinfunction "CONFIG[4]_B28") (pintype "input"))
      (node (ref "R112") (pin "2") (pinfunction "2_2") (pintype "passive"))
    )
    (net (code "45") (name "Net-(D12C-CONFIG[5])") (class "Default")
      (node (ref "D12") (pin "A32") (pinfunction "CONFIG[5]_A32") (pintype "input"))
      (node (ref "D12") (pin "B35") (pinfunction "LED_LINK10_B35") (pintype "output"))
      (node (ref "R107") (pin "2") (pinfunction "2_2") (pintype "passive"))
    )
    (net (code "46") (name "Net-(D12C-CONFIG[6])") (class "Default")
      (node (ref "D12") (pin "A37") (pinfunction "LED_RX_A37") (pintype "output"))
      (node (ref "D12") (pin "B27") (pinfunction "CONFIG[6]_B27") (pintype "input"))
      (node (ref "R116") (pin "2") (pinfunction "2_2") (pintype "passive"))
    )
    (net (code "47") (name "Net-(D12C-LED_LINK100)") (class "Default")
      (node (ref "D12") (pin "A40") (pinfunction "LED_LINK100_A40") (pintype "output"))
      (node (ref "R109") (pin "2") (pinfunction "2_2") (pintype "passive"))
    )
    (net (code "48") (name "Net-(D12C-LED_TX)") (class "Default")
      (node (ref "D12") (pin "B32") (pinfunction "LED_TX_B32") (pintype "output"))
      (node (ref "R115") (pin "2") (pinfunction "2_2") (pintype "passive"))
    )
    (net (code "49") (name "Net-(G12-EN)") (class "Default")
      (node (ref "G12") (pin "1") (pinfunction "EN_1") (pintype "passive"))
      (node (ref "R93") (pin "2") (pinfunction "2_2") (pintype "passive"))
    )
    (net (code "50") (name "Net-(VD1-K)") (class "Default")
      (node (ref "R107") (pin "1") (pinfunction "1_1") (pintype "passive"))
      (node (ref "VD1") (pin "1") (pinfunction "K_1") (pintype "passive"))
    )
    (net (code "51") (name "Net-(VD2-K)") (class "Default")
      (node (ref "R109") (pin "1") (pinfunction "1_1") (pintype "passive"))
      (node (ref "VD2") (pin "1") (pinfunction "K_1") (pintype "passive"))
    )
    (net (code "52") (name "Net-(VD3-K)") (class "Default")
      (node (ref "R112") (pin "1") (pinfunction "1_1") (pintype "passive"))
      (node (ref "VD3") (pin "1") (pinfunction "K_1") (pintype "passive"))
    )
    (net (code "53") (name "Net-(VD4-K)") (class "Default")
      (node (ref "R115") (pin "1") (pinfunction "1_1") (pintype "passive"))
      (node (ref "VD4") (pin "1") (pinfunction "K_1") (pintype "passive"))
    )
    (net (code "54") (name "Net-(VD5-K)") (class "Default")
      (node (ref "R116") (pin "1") (pinfunction "1_1") (pintype "passive"))
      (node (ref "VD5") (pin "1") (pinfunction "K_1") (pintype "passive"))
    )
    (net (code "55") (name "unconnected-(D12A-RXD0{slash}RD0-PadA51)") (class "Default")
      (node (ref "D12") (pin "A51") (pinfunction "RXD0/RD0_A51") (pintype "tri_state"))
    )
    (net (code "56") (name "unconnected-(D12A-RXD1{slash}RD1-PadB43)") (class "Default")
      (node (ref "D12") (pin "B43") (pinfunction "RXD1/RD1_B43") (pintype "tri_state"))
    )
    (net (code "57") (name "unconnected-(D12A-RXD2{slash}RD2-PadA50)") (class "Default")
      (node (ref "D12") (pin "A50") (pinfunction "RXD2/RD2_A50") (pintype "tri_state"))
    )
    (net (code "58") (name "unconnected-(D12A-RXD3{slash}RD3-PadA49)") (class "Default")
      (node (ref "D12") (pin "A49") (pinfunction "RXD3/RD3_A49") (pintype "tri_state"))
    )
    (net (code "59") (name "unconnected-(D12A-RXD4-PadB42)") (class "Default")
      (node (ref "D12") (pin "B42") (pinfunction "RXD4_B42") (pintype "tri_state"))
    )
    (net (code "60") (name "unconnected-(D12A-RXD5-PadA48)") (class "Default")
      (node (ref "D12") (pin "A48") (pinfunction "RXD5_A48") (pintype "tri_state"))
    )
    (net (code "61") (name "unconnected-(D12A-RXD6-PadA47)") (class "Default")
      (node (ref "D12") (pin "A47") (pinfunction "RXD6_A47") (pintype "tri_state"))
    )
    (net (code "62") (name "unconnected-(D12A-RXD7-PadB40)") (class "Default")
      (node (ref "D12") (pin "B40") (pinfunction "RXD7_B40") (pintype "tri_state"))
    )
    (net (code "63") (name "unconnected-(D12A-S_CLK+{slash}SD+-PadA43)") (class "Default")
      (node (ref "D12") (pin "A43") (pinfunction "S_CLK+/SD+_A43") (pintype "bidirectional"))
    )
    (net (code "64") (name "unconnected-(D12A-S_CLK-{slash}SD--PadB37)") (class "Default")
      (node (ref "D12") (pin "B37") (pinfunction "S_CLK-/SD-_B37") (pintype "bidirectional"))
    )
    (net (code "65") (name "unconnected-(D12B-125CLK-PadB11)") (class "Default")
      (node (ref "D12") (pin "B11") (pinfunction "125CLK_B11") (pintype "output"))
    )
    (net (code "66") (name "unconnected-(D12B-COL{slash}LPBK-PadA45)") (class "Default")
      (node (ref "D12") (pin "A45") (pinfunction "COL/LPBK_A45") (pintype "bidirectional"))
    )
    (net (code "67") (name "unconnected-(D12B-CRS{slash}COMMA-PadB39)") (class "Default")
      (node (ref "D12") (pin "B39") (pinfunction "CRS/COMMA_B39") (pintype "tri_state"))
    )
    (net (code "68") (name "unconnected-(D12B-HSDAC+-PadA20)") (class "Default")
      (node (ref "D12") (pin "A20") (pinfunction "HSDAC+_A20") (pintype "passive"))
    )
    (net (code "69") (name "unconnected-(D12B-HSDAC--PadB18)") (class "Default")
      (node (ref "D12") (pin "B18") (pinfunction "HSDAC-_B18") (pintype "passive"))
    )
    (net (code "70") (name "unconnected-(D12B-NC-PadA7)") (class "Default")
      (node (ref "D12") (pin "A7") (pinfunction "NC_A7") (pintype "passive"))
    )
    (net (code "71") (name "unconnected-(D12B-NC-PadA28)") (class "Default")
      (node (ref "D12") (pin "A28") (pinfunction "NC_A28") (pintype "passive"))
    )
    (net (code "72") (name "unconnected-(D12B-RX_CLK{slash}RCLK0{slash}RXC-PadB1)") (class "Default")
      (node (ref "D12") (pin "B1") (pinfunction "RX_CLK/RCLK0/RXC_B1") (pintype "tri_state"))
    )
    (net (code "73") (name "unconnected-(D12B-SEL_FREQ-PadB26)") (class "Default")
      (node (ref "D12") (pin "B26") (pinfunction "SEL_FREQ_B26") (pintype "input"))
    )
    (net (code "74") (name "unconnected-(D12B-TCK-PadA26)") (class "Default")
      (node (ref "D12") (pin "A26") (pinfunction "TCK_A26") (pintype "input"))
    )
    (net (code "75") (name "unconnected-(D12B-TDI-PadB21)") (class "Default")
      (node (ref "D12") (pin "B21") (pinfunction "TDI_B21") (pintype "input"))
    )
    (net (code "76") (name "unconnected-(D12B-TDO-PadA27)") (class "Default")
      (node (ref "D12") (pin "A27") (pinfunction "TDO_A27") (pintype "output"))
    )
    (net (code "77") (name "unconnected-(D12B-TMS-PadB22)") (class "Default")
      (node (ref "D12") (pin "B22") (pinfunction "TMS_B22") (pintype "input"))
    )
    (net (code "78") (name "unconnected-(D12B-XTAL2-PadB25)") (class "Default")
      (node (ref "D12") (pin "B25") (pinfunction "XTAL2_B25") (pintype "passive"))
    )
    (net (code "79") (name "unconnected-(D12C-GTX_CLK{slash}TBI_TXCLK{slash}TXC-PadB4)") (class "Default")
      (node (ref "D12") (pin "B4") (pinfunction "GTX_CLK/TBI_TXCLK/TXC_B4") (pintype "input"))
    )
    (net (code "80") (name "unconnected-(D12C-LED_DUPLEX-PadB33)") (class "Default")
      (node (ref "D12") (pin "B33") (pinfunction "LED_DUPLEX_B33") (pintype "output"))
    )
    (net (code "81") (name "unconnected-(D12C-RX_DV{slash}RXD8{slash}RX_CTL{slash}RD4_RD9-PadB44)") (class "Default")
      (node (ref "D12") (pin "B44") (pinfunction "RX_DV/RXD8/RX_CTL/RD4_RD9_B44") (pintype "tri_state"))
    )
    (net (code "82") (name "unconnected-(D12C-RX_ER{slash}RXD9-PadA2)") (class "Default")
      (node (ref "D12") (pin "A2") (pinfunction "RX_ER/RXD9_A2") (pintype "tri_state"))
    )
    (net (code "83") (name "unconnected-(D12C-TX_CLK{slash}RCLK1-PadB2)") (class "Default")
      (node (ref "D12") (pin "B2") (pinfunction "TX_CLK/RCLK1_B2") (pintype "tri_state"))
    )
    (net (code "84") (name "unconnected-(D12C-TX_EN{slash}TXD8{slash}TX_CTL{slash}TD4_TD9-PadA5)") (class "Default")
      (node (ref "D12") (pin "A5") (pinfunction "TX_EN/TXD8/TX_CTL/TD4_TD9_A5") (pintype "input"))
    )
    (net (code "85") (name "unconnected-(D12C-TX_ER{slash}TXD9-PadA4)") (class "Default")
      (node (ref "D12") (pin "A4") (pinfunction "TX_ER/TXD9_A4") (pintype "input"))
    )
  )
)
